# testovani_caroveho_senzoru.net
KiCad netlist of a schematic drawn in EAGLE
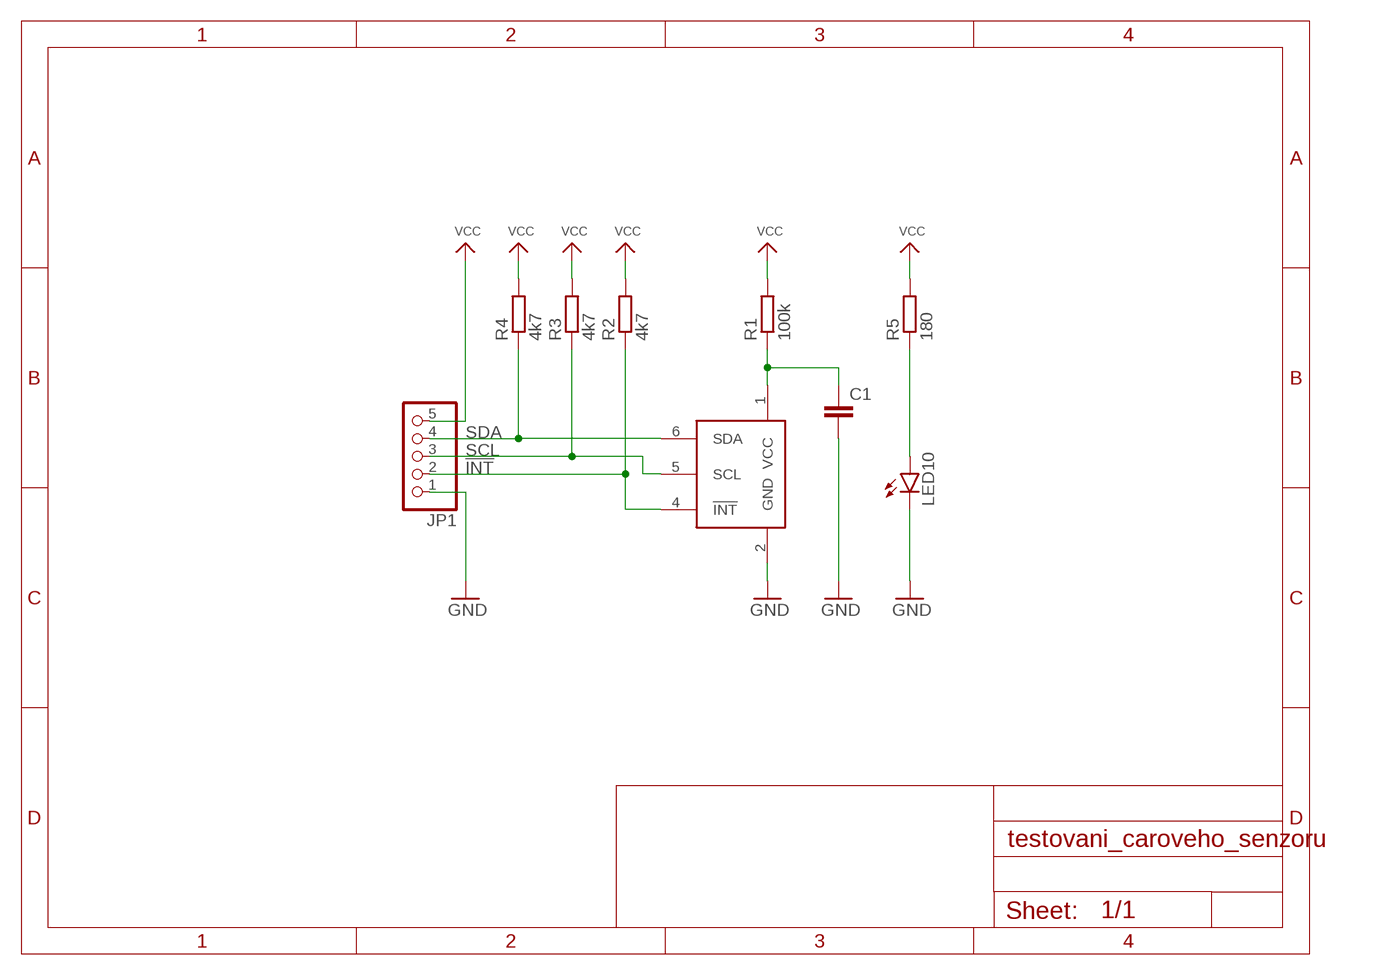
[diagram p0: schematic, sheet 1]

(export (version "E")
  (design (tool "Eeschema 10.0.6"))
  (components
    (comp (ref "C1")
      (value "C-EUC0603")
      (footprint "eagle-import:C0603")
      (libsource (lib "eagle-import") (part "C-EUC0603"))
    )
    (comp (ref "ISL10")
      (value "ISL29035")
      (footprint "eagle-import:ISL29035")
      (libsource (lib "eagle-import") (part "ISL29035"))
    )
    (comp (ref "JP1")
      (value "PINHD-1X5")
      (footprint "eagle-import:1X05")
      (libsource (lib "eagle-import") (part "PINHD-1X5"))
    )
    (comp (ref "LED10")
      (value "LEDCHIP-LED0603")
      (footprint "eagle-import:CHIP-LED0603")
      (libsource (lib "eagle-import") (part "LEDCHIP-LED0603"))
    )
    (comp (ref "R1")
      (value "100k")
      (footprint "eagle-import:R0402")
      (libsource (lib "eagle-import") (part "R-EU_R0402"))
    )
    (comp (ref "R2")
      (value "4k7")
      (footprint "eagle-import:R0402")
      (libsource (lib "eagle-import") (part "R-EU_R0402"))
    )
    (comp (ref "R3")
      (value "4k7")
      (footprint "eagle-import:R0402")
      (libsource (lib "eagle-import") (part "R-EU_R0402"))
    )
    (comp (ref "R4")
      (value "4k7")
      (footprint "eagle-import:R0402")
      (libsource (lib "eagle-import") (part "R-EU_R0402"))
    )
    (comp (ref "R5")
      (value "180")
      (footprint "eagle-import:R0402")
      (libsource (lib "eagle-import") (part "R-EU_R0402"))
    )
  )
  (nets
    (net (code "1") (name "/SCL") (class "Default")
      (node (ref "ISL10") (pin "5") (pinfunction "SCL_5") (pintype "bidirectional"))
      (node (ref "JP1") (pin "3") (pinfunction "3_3") (pintype "passive"))
      (node (ref "R3") (pin "1") (pinfunction "1_1") (pintype "passive"))
    )
    (net (code "2") (name "/SDA") (class "Default")
      (node (ref "ISL10") (pin "6") (pinfunction "SDA_6") (pintype "bidirectional"))
      (node (ref "JP1") (pin "4") (pinfunction "4_4") (pintype "passive"))
      (node (ref "R4") (pin "1") (pinfunction "1_1") (pintype "passive"))
    )
    (net (code "3") (name "/~{INT}") (class "Default")
      (node (ref "ISL10") (pin "4") (pinfunction "~{INT}_4") (pintype "bidirectional"))
      (node (ref "JP1") (pin "2") (pinfunction "2_2") (pintype "passive"))
      (node (ref "R2") (pin "1") (pinfunction "1_1") (pintype "passive"))
    )
    (net (code "4") (name "GND") (class "Default")
      (node (ref "C1") (pin "2") (pinfunction "2_2") (pintype "passive"))
      (node (ref "ISL10") (pin "2") (pinfunction "GND_2") (pintype "bidirectional"))
      (node (ref "JP1") (pin "1") (pinfunction "1_1") (pintype "passive"))
      (node (ref "LED10") (pin "C") (pinfunction "C_C") (pintype "passive"))
    )
    (net (code "5") (name "Net-(ISL10-VCC)") (class "Default")
      (node (ref "C1") (pin "1") (pinfunction "1_1") (pintype "passive"))
      (node (ref "ISL10") (pin "1") (pinfunction "VCC_1") (pintype "bidirectional"))
      (node (ref "R1") (pin "1") (pinfunction "1_1") (pintype "passive"))
    )
    (net (code "6") (name "Net-(LED10-PadA)") (class "Default")
      (node (ref "LED10") (pin "A") (pinfunction "A_A") (pintype "passive"))
      (node (ref "R5") (pin "1") (pinfunction "1_1") (pintype "passive"))
    )
    (net (code "7") (name "VCC") (class "Default")
      (node (ref "JP1") (pin "5") (pinfunction "5_5") (pintype "passive"))
      (node (ref "R1") (pin "2") (pinfunction "2_2") (pintype "passive"))
      (node (ref "R2") (pin "2") (pinfunction "2_2") (pintype "passive"))
      (node (ref "R3") (pin "2") (pinfunction "2_2") (pintype "passive"))
      (node (ref "R4") (pin "2") (pinfunction "2_2") (pintype "passive"))
      (node (ref "R5") (pin "2") (pinfunction "2_2") (pintype "passive"))
    )
  )
)
